# Power.net
KiCad netlist of a schematic drawn in Altium Designer
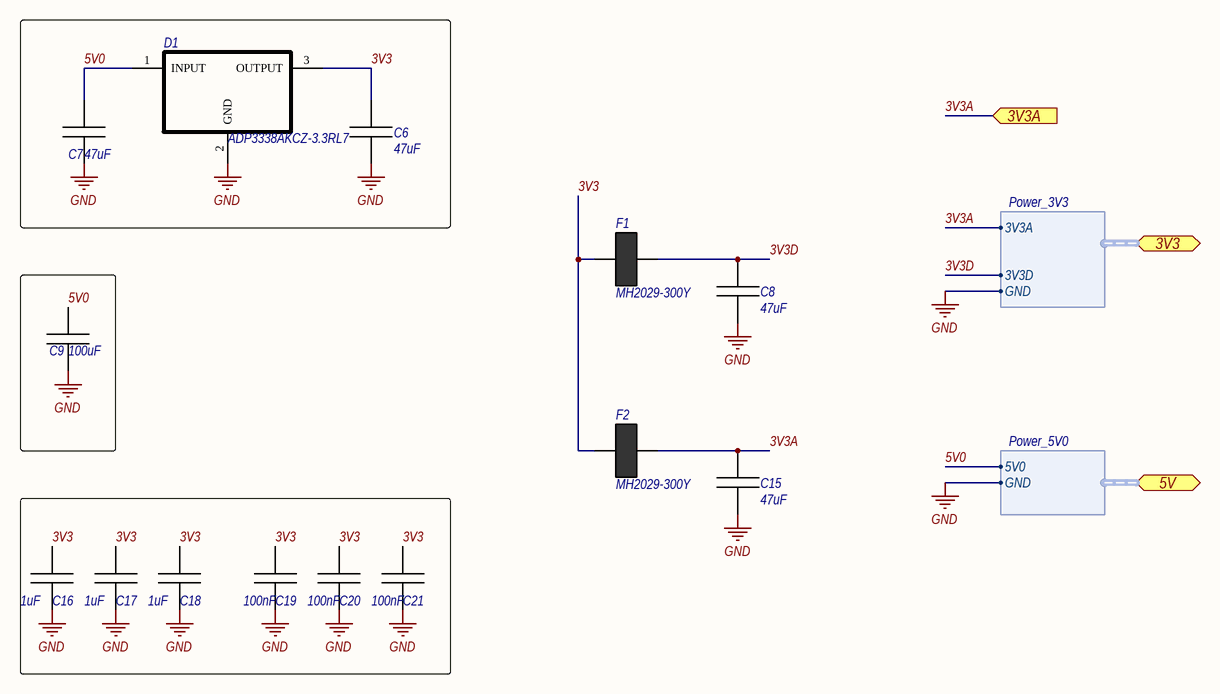
[diagram p0: Power.SchDoc]

(export (version "E")
  (design (tool "Eeschema 10.0.6"))
  (components
    (comp (ref "C6") (value "47uF") (libsource (lib "Passive") (part "Capacitor")))
    (comp (ref "C7") (value "47uF") (libsource (lib "Passive") (part "Capacitor")))
    (comp (ref "C8") (value "47uF") (libsource (lib "Passive") (part "Capacitor")))
    (comp (ref "C9") (value "100uF") (libsource (lib "Passive") (part "Capacitor")))
    (comp (ref "C15") (value "47uF") (libsource (lib "Passive") (part "Capacitor")))
    (comp (ref "C16") (value "1uF") (libsource (lib "Passive") (part "Capacitor")))
    (comp (ref "C17") (value "1uF") (libsource (lib "Passive") (part "Capacitor")))
    (comp (ref "C18") (value "1uF") (libsource (lib "Passive") (part "Capacitor")))
    (comp (ref "C19") (value "100nF") (libsource (lib "Passive") (part "Capacitor")))
    (comp (ref "C20") (value "100nF") (libsource (lib "Passive") (part "Capacitor")))
    (comp (ref "C21") (value "100nF") (libsource (lib "Passive") (part "Capacitor")))
    (comp (ref "D1")
      (value "ADP3338AKCZ-3.3RL7")
      (description "LDO")
      (libsource (lib "ic") (part "ADP3338AKCZ-3.3RL7"))
    )
    (comp (ref "F1") (value "MH2029-300Y") (libsource (lib "Passive") (part "Ferrite")))
    (comp (ref "F2") (value "MH2029-300Y") (libsource (lib "Passive") (part "Ferrite")))
  )
  (nets
    (net (code "3") (name "/3V3") (class "Default")
      (node (ref "C16") (pin "2") (pinfunction "2_2") (pintype "passive"))
      (node (ref "C17") (pin "2") (pinfunction "2_2") (pintype "passive"))
      (node (ref "C18") (pin "2") (pinfunction "2_2") (pintype "passive"))
      (node (ref "C19") (pin "2") (pinfunction "2_2") (pintype "passive"))
      (node (ref "C20") (pin "2") (pinfunction "2_2") (pintype "passive"))
      (node (ref "C21") (pin "2") (pinfunction "2_2") (pintype "passive"))
      (node (ref "C6") (pin "2") (pinfunction "2_2") (pintype "passive"))
      (node (ref "D1") (pin "3") (pinfunction "OUTPUT_3") (pintype "power_in"))
      (node (ref "F1") (pin "1") (pinfunction "1_1") (pintype "passive"))
      (node (ref "F2") (pin "1") (pinfunction "1_1") (pintype "passive"))
    )
    (net (code "4") (name "/3V3A") (class "Default")
      (node (ref "C15") (pin "2") (pinfunction "2_2") (pintype "passive"))
      (node (ref "F2") (pin "2") (pinfunction "2_2") (pintype "passive"))
    )
    (net (code "5") (name "/3V3D") (class "Default")
      (node (ref "C8") (pin "2") (pinfunction "2_2") (pintype "passive"))
      (node (ref "F1") (pin "2") (pinfunction "2_2") (pintype "passive"))
    )
    (net (code "6") (name "/5V0") (class "Default")
      (node (ref "C7") (pin "2") (pinfunction "2_2") (pintype "passive"))
      (node (ref "C9") (pin "2") (pinfunction "2_2") (pintype "passive"))
      (node (ref "D1") (pin "1") (pinfunction "INPUT_1") (pintype "power_in"))
    )
    (net (code "9") (name "GND") (class "Default")
      (node (ref "C15") (pin "1") (pinfunction "1_1") (pintype "passive"))
      (node (ref "C16") (pin "1") (pinfunction "1_1") (pintype "passive"))
      (node (ref "C17") (pin "1") (pinfunction "1_1") (pintype "passive"))
      (node (ref "C18") (pin "1") (pinfunction "1_1") (pintype "passive"))
      (node (ref "C19") (pin "1") (pinfunction "1_1") (pintype "passive"))
      (node (ref "C20") (pin "1") (pinfunction "1_1") (pintype "passive"))
      (node (ref "C21") (pin "1") (pinfunction "1_1") (pintype "passive"))
      (node (ref "C6") (pin "1") (pinfunction "1_1") (pintype "passive"))
      (node (ref "C7") (pin "1") (pinfunction "1_1") (pintype "passive"))
      (node (ref "C8") (pin "1") (pinfunction "1_1") (pintype "passive"))
      (node (ref "C9") (pin "1") (pinfunction "1_1") (pintype "passive"))
      (node (ref "D1") (pin "2") (pinfunction "GND_2") (pintype "passive"))
    )
  )
)
